# RC_Transmit_SCH.net
KiCad netlist of a schematic drawn in Altium Designer
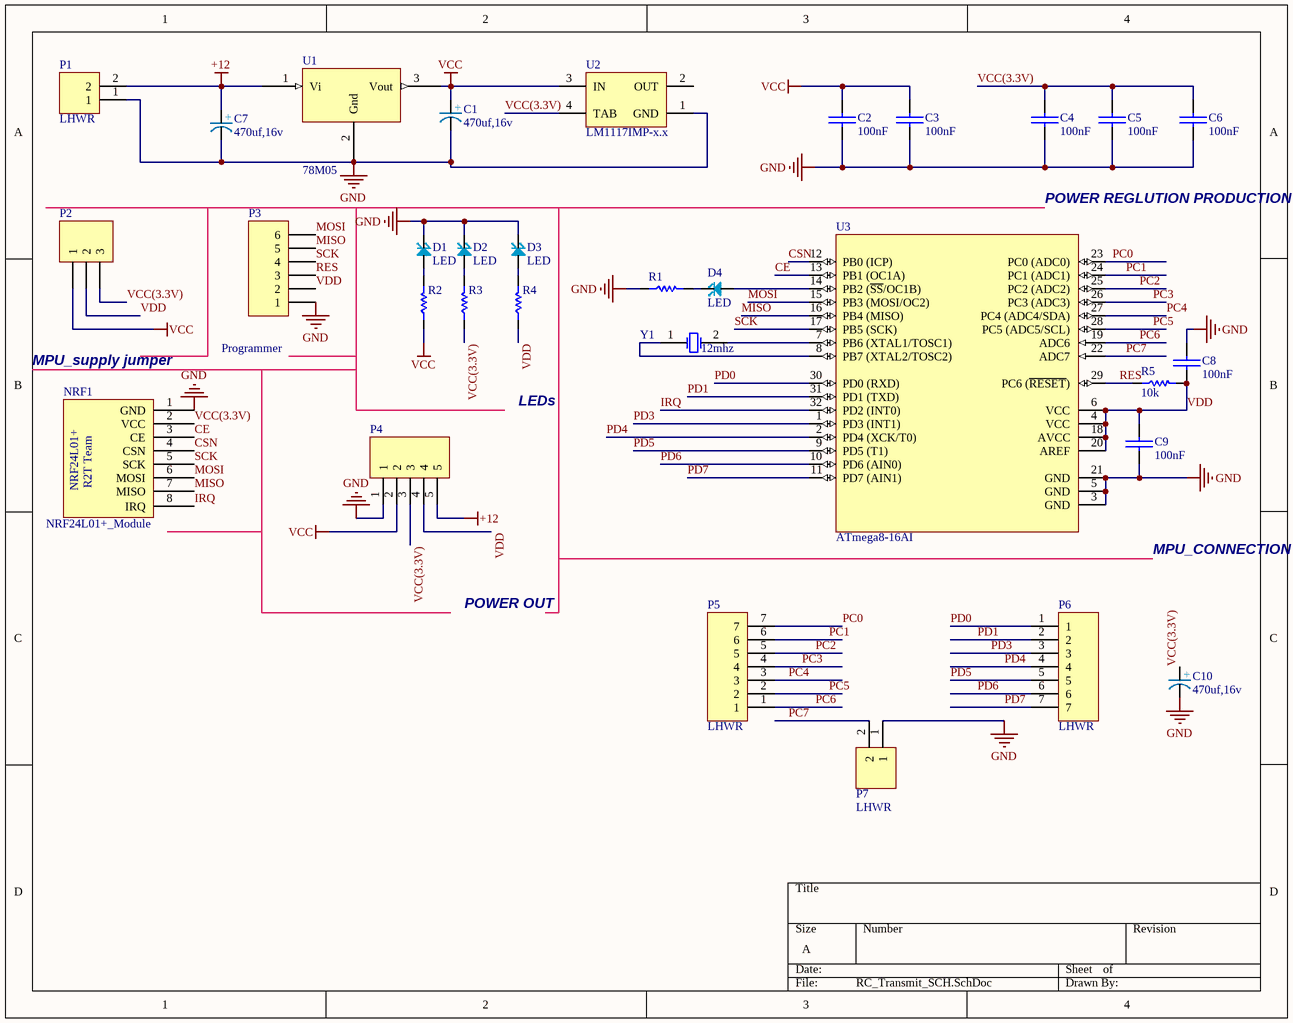
[diagram p0: RC_Transmit_SCH.SchDoc]

(export (version "E")
  (design (tool "Eeschema 10.0.6"))
  (components
    (comp (ref "C1")
      (value "Capacitor Polarized")
      (footprint "Electrolytic Capacitor SMD Dia-8")
      (fields (field (name "DESCRIPTION:") "470uf,16v") (field (name "DESIGNER") "Hamed Jafarzadeh ( R2T )"))
      (libsource (lib "R2T Team Library") (part "Capacitor Polarized"))
    )
    (comp (ref "C2")
      (value "100nF")
      (footprint "SMD_CAP_1206")
      (description "Bipolar Capacitor")
      (fields (field (name "VOLTAGE") "100V") (field (name "DESIGNER") "Saeid Jorablo"))
      (libsource (lib "My Library") (part "Cap-Bipolar"))
    )
    (comp (ref "C3")
      (value "100nF")
      (footprint "SMD_CAP_1206")
      (description "Bipolar Capacitor")
      (fields (field (name "VOLTAGE") "100V") (field (name "DESIGNER") "Saeid Jorablo"))
      (libsource (lib "My Library") (part "Cap-Bipolar"))
    )
    (comp (ref "C4")
      (value "100nF")
      (footprint "SMD_CAP_1206")
      (description "Bipolar Capacitor")
      (fields (field (name "VOLTAGE") "100V") (field (name "DESIGNER") "Saeid Jorablo"))
      (libsource (lib "My Library") (part "Cap-Bipolar"))
    )
    (comp (ref "C5")
      (value "100nF")
      (footprint "SMD_CAP_1206")
      (description "Bipolar Capacitor")
      (fields (field (name "VOLTAGE") "100V") (field (name "DESIGNER") "Saeid Jorablo"))
      (libsource (lib "My Library") (part "Cap-Bipolar"))
    )
    (comp (ref "C6")
      (value "100nF")
      (footprint "SMD_CAP_1206")
      (description "Bipolar Capacitor")
      (fields (field (name "VOLTAGE") "100V") (field (name "DESIGNER") "Saeid Jorablo"))
      (libsource (lib "My Library") (part "Cap-Bipolar"))
    )
    (comp (ref "C7")
      (value "Capacitor Polarized")
      (footprint "Electrolytic Capacitor SMD Dia-8")
      (fields (field (name "DESCRIPTION:") "470uf,16v") (field (name "DESIGNER") "Hamed Jafarzadeh ( R2T )"))
      (libsource (lib "") (part "Capacitor Polarized_1"))
    )
    (comp (ref "C8")
      (value "100nF")
      (footprint "SMD_CAP_1206")
      (description "Bipolar Capacitor")
      (fields (field (name "VOLTAGE") "100V") (field (name "DESIGNER") "Saeid Jorablo"))
      (libsource (lib "My Library") (part "Cap-Bipolar"))
    )
    (comp (ref "C9")
      (value "100nF")
      (footprint "SMD_CAP_1206")
      (description "Bipolar Capacitor")
      (fields (field (name "VOLTAGE") "100V") (field (name "DESIGNER") "Saeid Jorablo"))
      (libsource (lib "My Library") (part "Cap-Bipolar"))
    )
    (comp (ref "C10")
      (value "Capacitor Polarized")
      (footprint "Electrolytic Capacitor SMD Dia-8")
      (fields (field (name "DESCRIPTION:") "470uf,16v") (field (name "DESIGNER") "Hamed Jafarzadeh ( R2T )"))
      (libsource (lib "R2T Team Library") (part "Capacitor Polarized"))
    )
    (comp (ref "D1") (value "LED") (footprint "LED_5MM") (libsource (lib "My_lib_new") (part "LED")))
    (comp (ref "D2") (value "LED") (footprint "LED_5MM") (libsource (lib "My_lib_new") (part "LED")))
    (comp (ref "D3") (value "LED") (footprint "LED_5MM") (libsource (lib "My_lib_new") (part "LED")))
    (comp (ref "D4") (value "LED") (footprint "LED_5MM") (libsource (lib "My_lib_new") (part "LED")))
    (comp (ref "NRF1")
      (value "NRF24L01+_Module")
      (footprint "NRF24L01+_Module")
      (fields (field (name "DESIGNER:") "HamedJafarzadeh"))
      (libsource (lib "R2T Team Library") (part "NRF24L01+_Module"))
    )
    (comp (ref "P1")
      (value "LHWR")
      (footprint "Polarized Header 2")
      (fields (field (name "DESIGNER:") "Hamed Jafarzadeh - www.R2T.ir"))
      (libsource (lib "") (part "2pin LHWR_1"))
    )
    (comp (ref "P2")
      (value "Header 3")
      (footprint "HDR1X3")
      (description "Header, 3-Pin")
      (fields (field (name "PUBLISHER") "Altium Limited"))
      (libsource (lib "Miscellaneous Connectors") (part "Header 3"))
    )
    (comp (ref "P3")
      (value "Programmer")
      (footprint "HDR1X6")
      (description "Header, 6-Pin")
      (fields (field (name "PUBLISHER") "Altium Limited"))
      (libsource (lib "Miscellaneous Connectors") (part "Header 6"))
    )
    (comp (ref "P4")
      (value "LHWR")
      (footprint "Polarized Header 5")
      (fields (field (name "DESIGNER:") "Hamed Jafarzadeh - www.R2T.ir"))
      (libsource (lib "R2T Team Library") (part "5pin LHWR"))
    )
    (comp (ref "P5")
      (value "LHWR")
      (footprint "Polarized Header 7")
      (fields (field (name "DESIGNER:") "Hamed Jafarzadeh - www.R2T.ir"))
      (libsource (lib "R2T Team Library") (part "7pin LHWR"))
    )
    (comp (ref "P6")
      (value "LHWR")
      (footprint "Polarized Header 7")
      (fields (field (name "DESIGNER:") "Hamed Jafarzadeh - www.R2T.ir"))
      (libsource (lib "") (part "7pin LHWR_1"))
    )
    (comp (ref "P7")
      (value "LHWR")
      (footprint "Polarized Header 2")
      (fields (field (name "DESIGNER:") "Hamed Jafarzadeh - www.R2T.ir"))
      (libsource (lib "R2T Team Library") (part "2pin LHWR"))
    )
    (comp (ref "R1")
      (value "125/100")
      (footprint "RES 0805 (2012X06L)")
      (description "Resistor")
      (fields (field (name "TOLERANCE") "5%") (field (name "POWER") "1/8 W"))
      (libsource (lib "My Library") (part "Resistor"))
    )
    (comp (ref "R2")
      (value "100/125")
      (footprint "RES 0805 (2012X06L)")
      (description "Resistor")
      (fields (field (name "TOLERANCE") "5%") (field (name "POWER") "1/8 W"))
      (libsource (lib "My Library") (part "Resistor"))
    )
    (comp (ref "R3")
      (value "100/125")
      (footprint "RES 0805 (2012X06L)")
      (description "Resistor")
      (fields (field (name "TOLERANCE") "5%") (field (name "POWER") "1/8 W"))
      (libsource (lib "My Library") (part "Resistor"))
    )
    (comp (ref "R4")
      (value "100/125")
      (footprint "RES 0805 (2012X06L)")
      (description "Resistor")
      (fields (field (name "TOLERANCE") "5%") (field (name "POWER") "1/8 W"))
      (libsource (lib "My Library") (part "Resistor"))
    )
    (comp (ref "R5")
      (value "10k")
      (footprint "RES 0805 (2012X06L)")
      (description "Resistor")
      (libsource (lib "My Library") (part "Resistor"))
    )
    (comp (ref "U1")
      (value "78M05")
      (footprint "DPAK228P972X240-3N")
      (libsource (lib "R2T Team Library") (part "78M05"))
    )
    (comp (ref "U2")
      (value "LM1117IMP-x.x")
      (footprint "MP04A_N")
      (description "x.x Volt, 800mA Low-Dropout Linear Regulator, 4-pin SOT-223")
      (fields
        (field (name "PARTNUMBER") "LM1117IMP-3.3")
        (field (name "MANUFACTURER") "National Semiconductor")
        (field (name "PUBLISHER") "Altium Limited")
      )
      (libsource (lib "My Library") (part "LM1117IMP-x.x"))
    )
    (comp (ref "U3")
      (value "ATmega8-16AI")
      (footprint "My_32A_M")
      (description "AVR 8K Bytes of In-System Programmable Flash Memory")
      (fields (field (name "PUBLISHER") "Altium Limited"))
      (libsource (lib "Mylib") (part "ATmega8-16AI"))
    )
    (comp (ref "Y1")
      (value "12mhz")
      (footprint "XTAL Small")
      (description "XTAL Crystal")
      (libsource (lib "My Library") (part "XTAL"))
    )
  )
  (nets
    (net (code "1") (name "+12") (class "Default")
      (node (ref "C7") (pin "1") (pintype "passive"))
      (node (ref "P1") (pin "2") (pinfunction "2_2") (pintype "passive"))
      (node (ref "P4") (pin "5") (pinfunction "5_5") (pintype "passive"))
      (node (ref "U1") (pin "1") (pinfunction "Vi_1") (pintype "input"))
    )
    (net (code "2") (name "/CE") (class "Default")
      (node (ref "NRF1") (pin "3") (pinfunction "CE_3") (pintype "passive"))
      (node (ref "U3") (pin "13") (pinfunction "PB1_(OC1A)_13") (pintype "bidirectional"))
    )
    (net (code "3") (name "/CSN") (class "Default")
      (node (ref "NRF1") (pin "4") (pinfunction "CSN_4") (pintype "passive"))
      (node (ref "U3") (pin "12") (pinfunction "PB0_(ICP)_12") (pintype "bidirectional"))
    )
    (net (code "4") (name "/IRQ") (class "Default")
      (node (ref "NRF1") (pin "8") (pinfunction "IRQ_8") (pintype "passive"))
      (node (ref "U3") (pin "32") (pinfunction "PD2_(INT0)_32") (pintype "bidirectional"))
    )
    (net (code "5") (name "/MISO") (class "Default")
      (node (ref "NRF1") (pin "7") (pinfunction "MISO_7") (pintype "passive"))
      (node (ref "P3") (pin "5") (pinfunction "5_5") (pintype "passive"))
      (node (ref "U3") (pin "16") (pinfunction "PB4_(MISO)_16") (pintype "bidirectional"))
    )
    (net (code "6") (name "/MOSI") (class "Default")
      (node (ref "NRF1") (pin "6") (pinfunction "MOSI_6") (pintype "passive"))
      (node (ref "P3") (pin "6") (pinfunction "6_6") (pintype "passive"))
      (node (ref "U3") (pin "15") (pinfunction "PB3_(MOSI/OC2)_15") (pintype "bidirectional"))
    )
    (net (code "7") (name "/PC0") (class "Default")
      (node (ref "P5") (pin "7") (pinfunction "7_7") (pintype "passive"))
      (node (ref "U3") (pin "23") (pinfunction "PC0_(ADC0)_23") (pintype "bidirectional"))
    )
    (net (code "8") (name "/PC1") (class "Default")
      (node (ref "P5") (pin "6") (pinfunction "6_6") (pintype "passive"))
      (node (ref "U3") (pin "24") (pinfunction "PC1_(ADC1)_24") (pintype "bidirectional"))
    )
    (net (code "9") (name "/PC2") (class "Default")
      (node (ref "P5") (pin "5") (pinfunction "5_5") (pintype "passive"))
      (node (ref "U3") (pin "25") (pinfunction "PC2_(ADC2)_25") (pintype "bidirectional"))
    )
    (net (code "10") (name "/PC3") (class "Default")
      (node (ref "P5") (pin "4") (pinfunction "4_4") (pintype "passive"))
      (node (ref "U3") (pin "26") (pinfunction "PC3_(ADC3)_26") (pintype "bidirectional"))
    )
    (net (code "11") (name "/PC4") (class "Default")
      (node (ref "P5") (pin "3") (pinfunction "3_3") (pintype "passive"))
      (node (ref "U3") (pin "27") (pinfunction "PC4_(ADC4/SDA)_27") (pintype "bidirectional"))
    )
    (net (code "12") (name "/PC5") (class "Default")
      (node (ref "P5") (pin "2") (pinfunction "2_2") (pintype "passive"))
      (node (ref "U3") (pin "28") (pinfunction "PC5_(ADC5/SCL)_28") (pintype "bidirectional"))
    )
    (net (code "13") (name "/PC6") (class "Default")
      (node (ref "P5") (pin "1") (pinfunction "1_1") (pintype "passive"))
      (node (ref "U3") (pin "19") (pinfunction "ADC6_19") (pintype "input"))
    )
    (net (code "14") (name "/PC7") (class "Default")
      (node (ref "P7") (pin "2") (pinfunction "2_2") (pintype "passive"))
      (node (ref "U3") (pin "22") (pinfunction "ADC7_22") (pintype "input"))
    )
    (net (code "15") (name "/PD0") (class "Default")
      (node (ref "P6") (pin "1") (pinfunction "1_1") (pintype "passive"))
      (node (ref "U3") (pin "30") (pinfunction "PD0_(RXD)_30") (pintype "bidirectional"))
    )
    (net (code "16") (name "/PD1") (class "Default")
      (node (ref "P6") (pin "2") (pinfunction "2_2") (pintype "passive"))
      (node (ref "U3") (pin "31") (pinfunction "PD1_(TXD)_31") (pintype "bidirectional"))
    )
    (net (code "17") (name "/PD3") (class "Default")
      (node (ref "P6") (pin "3") (pinfunction "3_3") (pintype "passive"))
      (node (ref "U3") (pin "1") (pinfunction "PD3_(INT1)_1") (pintype "bidirectional"))
    )
    (net (code "18") (name "/PD4") (class "Default")
      (node (ref "P6") (pin "4") (pinfunction "4_4") (pintype "passive"))
      (node (ref "U3") (pin "2") (pinfunction "PD4_(XCK/T0)_2") (pintype "bidirectional"))
    )
    (net (code "19") (name "/PD5") (class "Default")
      (node (ref "P6") (pin "5") (pinfunction "5_5") (pintype "passive"))
      (node (ref "U3") (pin "9") (pinfunction "PD5_(T1)_9") (pintype "bidirectional"))
    )
    (net (code "20") (name "/PD6") (class "Default")
      (node (ref "P6") (pin "6") (pinfunction "6_6") (pintype "passive"))
      (node (ref "U3") (pin "10") (pinfunction "PD6_(AIN0)_10") (pintype "bidirectional"))
    )
    (net (code "21") (name "/PD7") (class "Default")
      (node (ref "P6") (pin "7") (pinfunction "7_7") (pintype "passive"))
      (node (ref "U3") (pin "11") (pinfunction "PD7_(AIN1)_11") (pintype "bidirectional"))
    )
    (net (code "22") (name "/RES") (class "Default")
      (node (ref "P3") (pin "3") (pinfunction "3_3") (pintype "passive"))
      (node (ref "R5") (pin "1") (pinfunction "1_1") (pintype "passive"))
      (node (ref "U3") (pin "29") (pinfunction "PC6_(~{RESET})_29") (pintype "bidirectional"))
    )
    (net (code "23") (name "/SCK") (class "Default")
      (node (ref "NRF1") (pin "5") (pinfunction "SCK_5") (pintype "passive"))
      (node (ref "P3") (pin "4") (pinfunction "4_4") (pintype "passive"))
      (node (ref "U3") (pin "17") (pinfunction "PB5_(SCK)_17") (pintype "bidirectional"))
    )
    (net (code "24") (name "/VCC(3.3V)") (class "Default")
      (node (ref "C10") (pin "1") (pintype "passive"))
      (node (ref "C4") (pin "1") (pinfunction "+_1") (pintype "passive"))
      (node (ref "C5") (pin "1") (pinfunction "+_1") (pintype "passive"))
      (node (ref "C6") (pin "1") (pinfunction "+_1") (pintype "passive"))
      (node (ref "NRF1") (pin "2") (pinfunction "VCC_2") (pintype "passive"))
      (node (ref "P2") (pin "3") (pinfunction "3_3") (pintype "passive"))
      (node (ref "P4") (pin "3") (pinfunction "3_3") (pintype "passive"))
      (node (ref "R3") (pin "1") (pinfunction "1_1") (pintype "passive"))
      (node (ref "U2") (pin "4") (pinfunction "TAB_4") (pintype "power_in"))
    )
    (net (code "25") (name "/VDD") (class "Default")
      (node (ref "C8") (pin "1") (pinfunction "+_1") (pintype "passive"))
      (node (ref "C9") (pin "1") (pinfunction "+_1") (pintype "passive"))
      (node (ref "P2") (pin "2") (pinfunction "2_2") (pintype "passive"))
      (node (ref "P3") (pin "2") (pinfunction "2_2") (pintype "passive"))
      (node (ref "P4") (pin "4") (pinfunction "4_4") (pintype "passive"))
      (node (ref "R4") (pin "1") (pinfunction "1_1") (pintype "passive"))
      (node (ref "R5") (pin "2") (pinfunction "2_2") (pintype "passive"))
      (node (ref "U3") (pin "18") (pinfunction "AVCC_18") (pintype "power_in"))
      (node (ref "U3") (pin "20") (pinfunction "AREF_20") (pintype "passive"))
      (node (ref "U3") (pin "4") (pinfunction "VCC_4") (pintype "power_in"))
      (node (ref "U3") (pin "6") (pinfunction "VCC_6") (pintype "power_in"))
    )
    (net (code "26") (name "GND") (class "Default")
      (node (ref "C1") (pin "2") (pintype "passive"))
      (node (ref "C10") (pin "2") (pintype "passive"))
      (node (ref "C2") (pin "2") (pinfunction "-_2") (pintype "passive"))
      (node (ref "C3") (pin "2") (pinfunction "-_2") (pintype "passive"))
      (node (ref "C4") (pin "2") (pinfunction "-_2") (pintype "passive"))
      (node (ref "C5") (pin "2") (pinfunction "-_2") (pintype "passive"))
      (node (ref "C6") (pin "2") (pinfunction "-_2") (pintype "passive"))
      (node (ref "C7") (pin "2") (pintype "passive"))
      (node (ref "C8") (pin "2") (pinfunction "-_2") (pintype "passive"))
      (node (ref "C9") (pin "2") (pinfunction "-_2") (pintype "passive"))
      (node (ref "D1") (pin "2") (pintype "passive"))
      (node (ref "D2") (pin "2") (pintype "passive"))
      (node (ref "D3") (pin "2") (pintype "passive"))
      (node (ref "NRF1") (pin "1") (pinfunction "GND_1") (pintype "passive"))
      (node (ref "P1") (pin "1") (pinfunction "1_1") (pintype "passive"))
      (node (ref "P3") (pin "1") (pinfunction "1_1") (pintype "passive"))
      (node (ref "P4") (pin "1") (pinfunction "1_1") (pintype "passive"))
      (node (ref "P7") (pin "1") (pinfunction "1_1") (pintype "passive"))
      (node (ref "R1") (pin "1") (pinfunction "1_1") (pintype "passive"))
      (node (ref "U1") (pin "2") (pinfunction "Gnd_2") (pintype "passive"))
      (node (ref "U2") (pin "1") (pinfunction "GND_1") (pintype "power_in"))
      (node (ref "U3") (pin "21") (pinfunction "GND_21") (pintype "power_in"))
      (node (ref "U3") (pin "3") (pinfunction "GND_3") (pintype "power_in"))
      (node (ref "U3") (pin "5") (pinfunction "GND_5") (pintype "power_in"))
    )
    (net (code "27") (name "Net-(D1-Pad1)") (class "Default")
      (node (ref "D1") (pin "1") (pintype "passive"))
      (node (ref "R2") (pin "2") (pinfunction "2_2") (pintype "passive"))
    )
    (net (code "28") (name "Net-(D2-Pad1)") (class "Default")
      (node (ref "D2") (pin "1") (pintype "passive"))
      (node (ref "R3") (pin "2") (pinfunction "2_2") (pintype "passive"))
    )
    (net (code "29") (name "Net-(D3-Pad1)") (class "Default")
      (node (ref "D3") (pin "1") (pintype "passive"))
      (node (ref "R4") (pin "2") (pinfunction "2_2") (pintype "passive"))
    )
    (net (code "30") (name "Net-(D4-Pad2)") (class "Default")
      (node (ref "D4") (pin "2") (pintype "passive"))
      (node (ref "R1") (pin "2") (pinfunction "2_2") (pintype "passive"))
    )
    (net (code "31") (name "Net-(U3-PB2_(~{SS}{slash}OC1B))") (class "Default")
      (node (ref "D4") (pin "1") (pintype "passive"))
      (node (ref "U3") (pin "14") (pinfunction "PB2_(~{SS}/OC1B)_14") (pintype "bidirectional"))
    )
    (net (code "32") (name "Net-(U3-PB6_(XTAL1{slash}TOSC1))") (class "Default")
      (node (ref "U3") (pin "7") (pinfunction "PB6_(XTAL1/TOSC1)_7") (pintype "bidirectional"))
      (node (ref "Y1") (pin "2") (pinfunction "OSC2_2") (pintype "passive"))
    )
    (net (code "33") (name "Net-(U3-PB7_(XTAL2{slash}TOSC2))") (class "Default")
      (node (ref "U3") (pin "8") (pinfunction "PB7_(XTAL2/TOSC2)_8") (pintype "bidirectional"))
      (node (ref "Y1") (pin "1") (pinfunction "OSC1_1") (pintype "passive"))
    )
    (net (code "34") (name "VCC") (class "Default")
      (node (ref "C1") (pin "1") (pintype "passive"))
      (node (ref "C2") (pin "1") (pinfunction "+_1") (pintype "passive"))
      (node (ref "C3") (pin "1") (pinfunction "+_1") (pintype "passive"))
      (node (ref "P2") (pin "1") (pinfunction "1_1") (pintype "passive"))
      (node (ref "P4") (pin "2") (pinfunction "2_2") (pintype "passive"))
      (node (ref "R2") (pin "1") (pinfunction "1_1") (pintype "passive"))
      (node (ref "U1") (pin "3") (pinfunction "Vout_3") (pintype "output"))
      (node (ref "U2") (pin "3") (pinfunction "IN_3") (pintype "power_in"))
    )
    (net (code "35") (name "unconnected-(U2-OUT-Pad2)") (class "Default")
      (node (ref "U2") (pin "2") (pinfunction "OUT_2") (pintype "power_in"))
    )
  )
)
